# v1_bluetooth-20x20.net
KiCad netlist of a schematic drawn in EAGLE
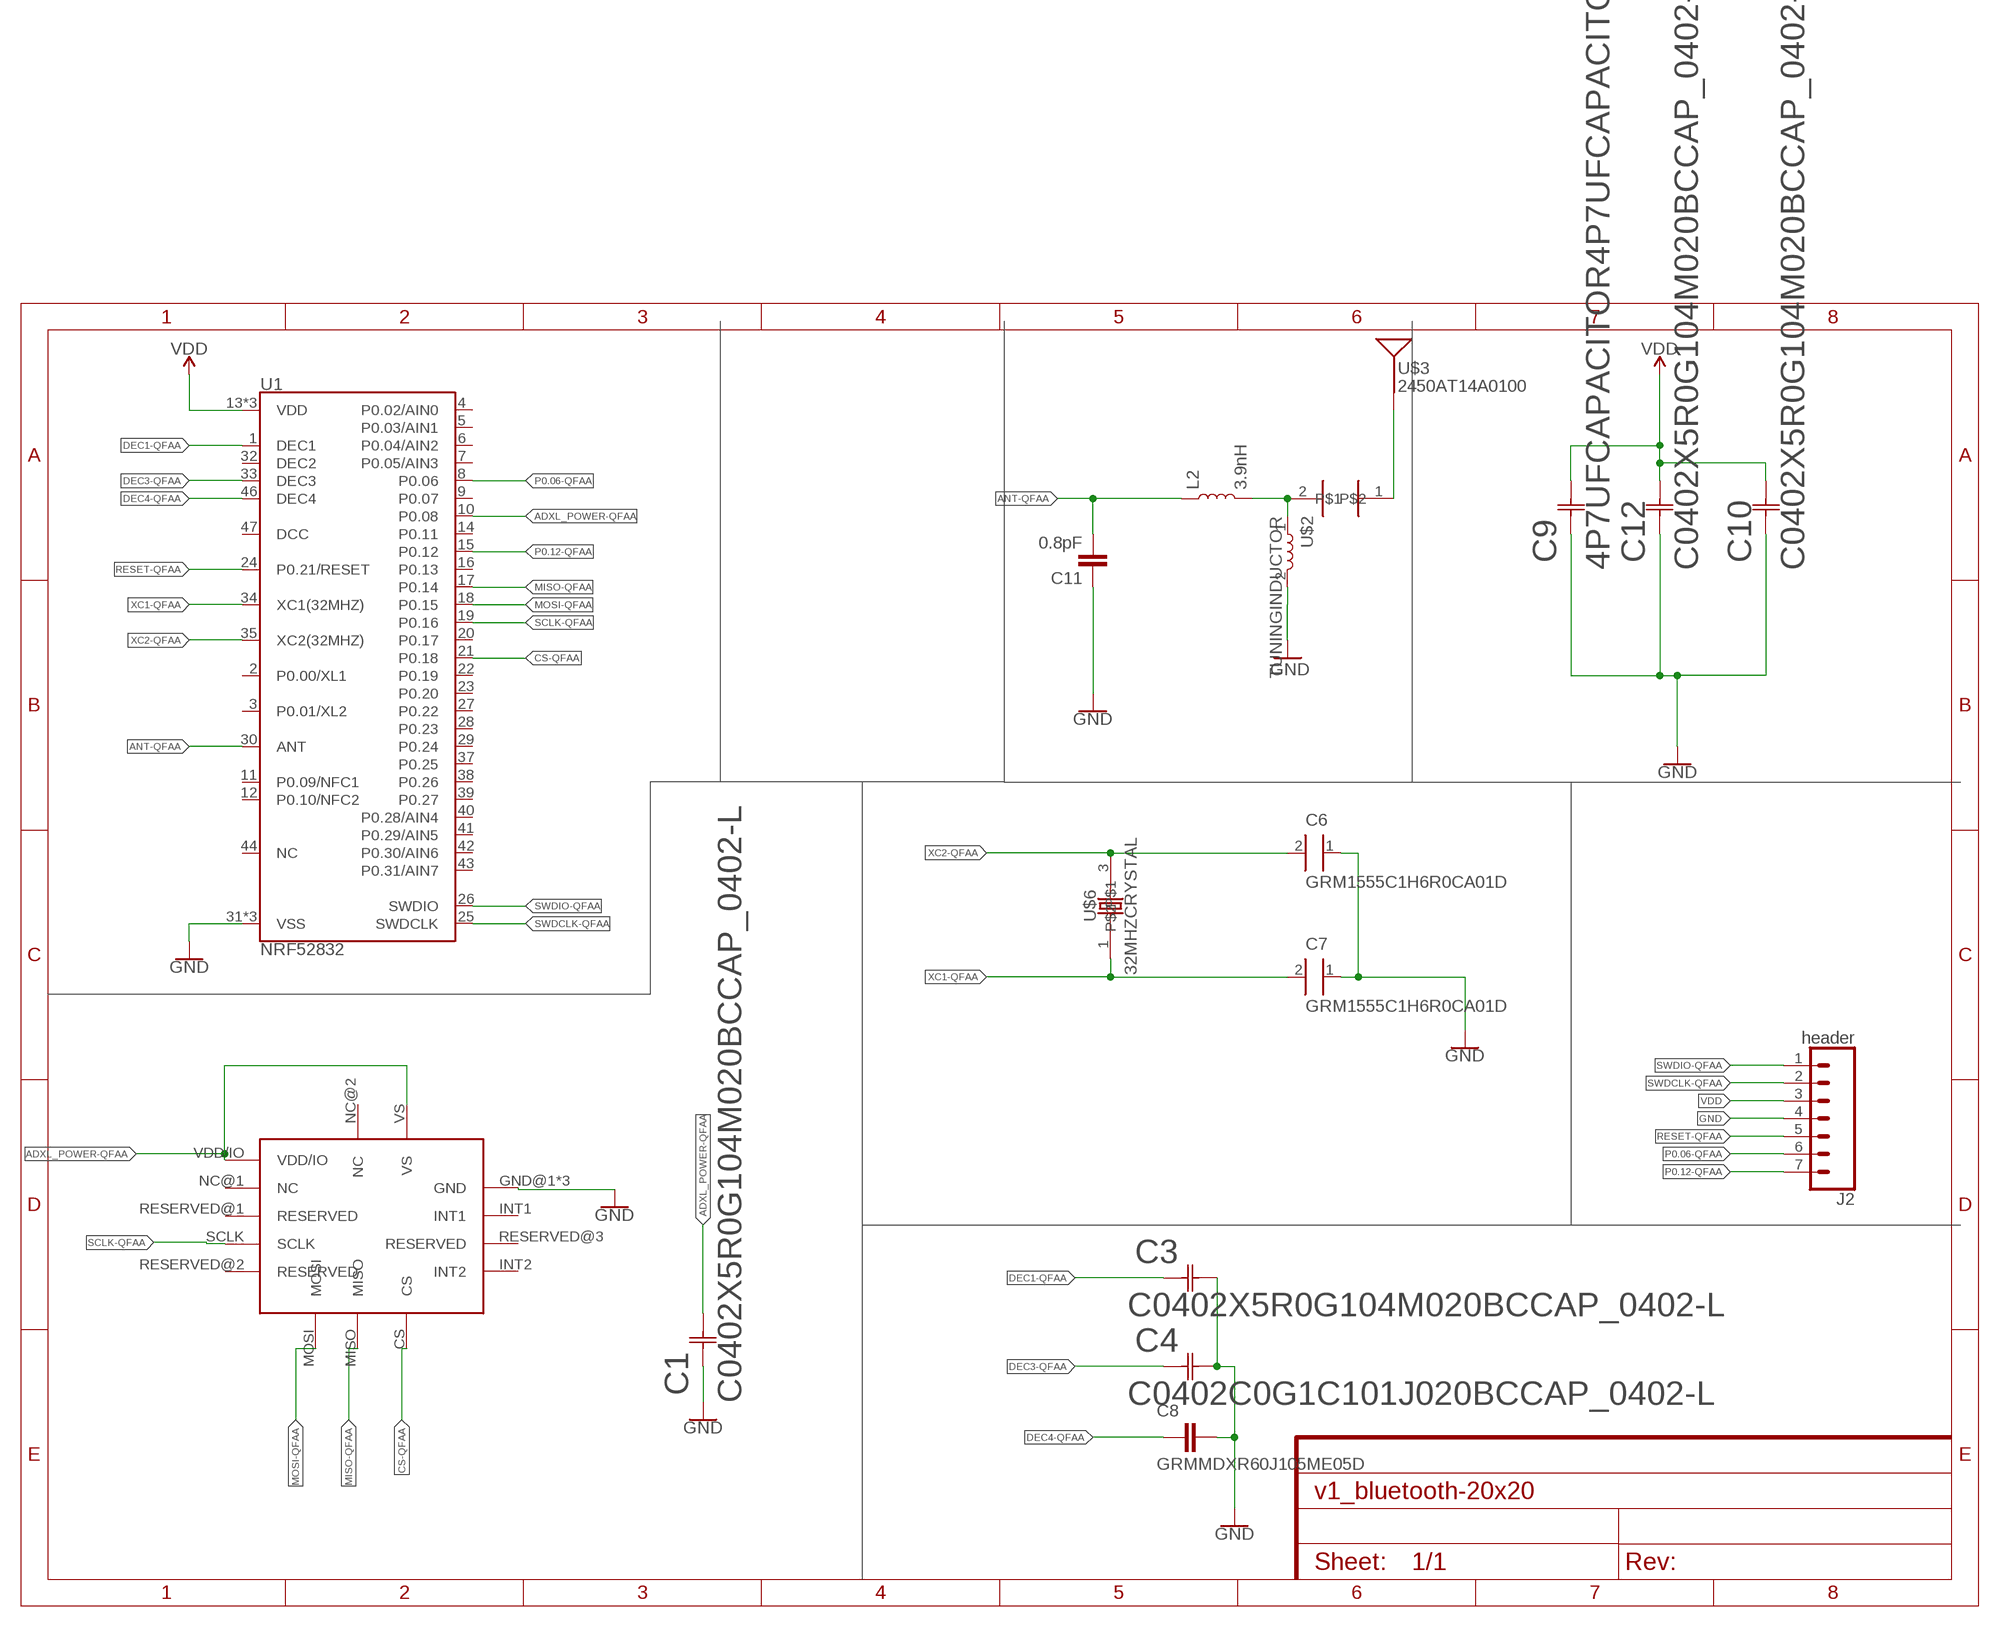
[diagram p0: schematic, sheet 1]

(export (version "E")
  (design (tool "Eeschema 10.0.6"))
  (components
    (comp (ref "C1")
      (value "C0402X5R0G104M020BCCAP_0402-L")
      (footprint "eagle-import:CAP_0402-L")
      (fields (field (name "MANUFACTURER_PART_NUMBER") "C0402C0G1C101J020BC"))
      (libsource (lib "eagle-import") (part "C0402X5R0G104M020BCCAP_0402-L"))
    )
    (comp (ref "C3")
      (value "C0402X5R0G104M020BCCAP_0402-L")
      (footprint "eagle-import:CAP_0402-L")
      (fields (field (name "MANUFACTURER_PART_NUMBER") "C0402C0G1C101J020BC"))
      (libsource (lib "eagle-import") (part "C0402X5R0G104M020BCCAP_0402-L"))
    )
    (comp (ref "C4")
      (value "C0402C0G1C101J020BCCAP_0402-L")
      (footprint "eagle-import:CAP_0402-L")
      (fields (field (name "MANUFACTURER_PART_NUMBER") "C0402C0G1C101J020BC"))
      (libsource (lib "eagle-import") (part "C0402C0G1C101J020BCCAP_0402-L"))
    )
    (comp (ref "C6")
      (value "GRM1555C1H6R0CA01D")
      (footprint "eagle-import:CAPC1005X55N")
      (fields (field (name "DIGI-KEY_PART_NUMBER") "490-8222-1-ND") (field (name "MF") "Murata"))
      (libsource (lib "eagle-import") (part "GRM1555C1H6R0CA01D"))
    )
    (comp (ref "C7")
      (value "GRM1555C1H6R0CA01D")
      (footprint "eagle-import:CAPC1005X55N")
      (fields (field (name "DIGI-KEY_PART_NUMBER") "490-8222-1-ND") (field (name "MF") "Murata"))
      (libsource (lib "eagle-import") (part "GRM1555C1H6R0CA01D"))
    )
    (comp (ref "C8")
      (value "GRMMDXR60J105ME05D")
      (footprint "eagle-import:CAPC0502X28N")
      (fields (field (name "DIGI-KEY_PART_NUMBER") "490-13424-1-ND") (field (name "MF") "Murata"))
      (libsource (lib "eagle-import") (part "GRMMDXR60J105ME05D"))
    )
    (comp (ref "C9")
      (value "4P7UFCAPACITOR4P7UFCAPACITOR")
      (footprint "eagle-import:4P7UFCAPACITOR")
      (fields (field (name "MANUFACTURER_PART_NUMBER") "C0816X5R0J475M050AC"))
      (libsource (lib "eagle-import") (part "4P7UFCAPACITOR4P7UFCAPACITOR"))
    )
    (comp (ref "C10")
      (value "C0402X5R0G104M020BCCAP_0402-L")
      (footprint "eagle-import:CAP_0402-L")
      (fields (field (name "MANUFACTURER_PART_NUMBER") "C0402C0G1C101J020BC"))
      (libsource (lib "eagle-import") (part "C0402X5R0G104M020BCCAP_0402-L"))
    )
    (comp (ref "C11")
      (value "0.8pF")
      (footprint "eagle-import:0402")
      (libsource (lib "eagle-import") (part "0.8PF-0402-50V-0.1PF"))
    )
    (comp (ref "C12")
      (value "C0402X5R0G104M020BCCAP_0402-L")
      (footprint "eagle-import:CAP_0402-L")
      (fields (field (name "MANUFACTURER_PART_NUMBER") "C0402C0G1C101J020BC"))
      (libsource (lib "eagle-import") (part "C0402X5R0G104M020BCCAP_0402-L"))
    )
    (comp (ref "J2")
      (value "header")
      (footprint "eagle-import:1X07")
      (libsource (lib "eagle-import") (part "CONN_07"))
    )
    (comp (ref "L2")
      (value "3.9nH")
      (footprint "eagle-import:0402")
      (libsource (lib "eagle-import") (part "INDUCTOR-0402-3.9NH"))
    )
    (comp (ref "U$1")
      (value "ADXL362")
      (footprint "eagle-import:TFLGA-16_3.3MMX3.1MM")
      (libsource (lib "eagle-import") (part "ADXL362"))
    )
    (comp (ref "U$2")
      (value "TUNINGINDUCTOR")
      (footprint "eagle-import:0402")
      (libsource (lib "eagle-import") (part "TUNINGINDUCTOR"))
    )
    (comp (ref "U$3")
      (value "2450AT14A0100")
      (footprint "eagle-import:2450AT14A0100")
      (libsource (lib "eagle-import") (part "2450AT14A0100"))
    )
    (comp (ref "U$5")
      (value "0402-1005")
      (footprint "eagle-import:0402-1005")
      (libsource (lib "eagle-import") (part "0402-1005"))
    )
    (comp (ref "U$6")
      (value "32MHZCRYSTAL")
      (footprint "eagle-import:32MHZCRYSTAL")
      (libsource (lib "eagle-import") (part "32MHZCRYSTAL"))
    )
    (comp (ref "U1")
      (value "NRF52832")
      (footprint "eagle-import:QFN48-6X6MM")
      (libsource (lib "eagle-import") (part "NRF52832"))
    )
  )
  (nets
    (net (code "1") (name "ADXL_POWER-QFAA") (class "Default")
      (node (ref "C1") (pin "2") (pinfunction "22_2") (pintype "passive"))
      (node (ref "U$1") (pin "VDD/IO") (pinfunction "VDD/IO_VDD/IO") (pintype "bidirectional"))
      (node (ref "U$1") (pin "VS") (pinfunction "VS_VS") (pintype "bidirectional"))
      (node (ref "U1") (pin "10") (pinfunction "P0.08_10") (pintype "bidirectional"))
    )
    (net (code "2") (name "ANT-QFAA") (class "Default")
      (node (ref "C11") (pin "2") (pinfunction "2_2") (pintype "passive"))
      (node (ref "L2") (pin "1") (pinfunction "1_1") (pintype "passive"))
      (node (ref "U1") (pin "30") (pinfunction "ANT_30") (pintype "bidirectional"))
    )
    (net (code "3") (name "CS-QFAA") (class "Default")
      (node (ref "U$1") (pin "CS") (pinfunction "CS_CS") (pintype "bidirectional"))
      (node (ref "U1") (pin "21") (pinfunction "P0.18_21") (pintype "bidirectional"))
    )
    (net (code "4") (name "DEC1-QFAA") (class "Default")
      (node (ref "C3") (pin "1") (pinfunction "11_1") (pintype "passive"))
      (node (ref "U1") (pin "1") (pinfunction "DEC1_1") (pintype "bidirectional"))
    )
    (net (code "5") (name "DEC3-QFAA") (class "Default")
      (node (ref "C4") (pin "1") (pinfunction "11_1") (pintype "passive"))
      (node (ref "U1") (pin "33") (pinfunction "DEC3_33") (pintype "bidirectional"))
    )
    (net (code "6") (name "DEC4-QFAA") (class "Default")
      (node (ref "C8") (pin "1") (pinfunction "1_1") (pintype "passive"))
      (node (ref "U1") (pin "46") (pinfunction "DEC4_46") (pintype "bidirectional"))
    )
    (net (code "7") (name "GND") (class "Default")
      (node (ref "C1") (pin "1") (pinfunction "11_1") (pintype "passive"))
      (node (ref "C10") (pin "1") (pinfunction "11_1") (pintype "passive"))
      (node (ref "C11") (pin "1") (pinfunction "1_1") (pintype "passive"))
      (node (ref "C12") (pin "1") (pinfunction "11_1") (pintype "passive"))
      (node (ref "C3") (pin "2") (pinfunction "22_2") (pintype "passive"))
      (node (ref "C4") (pin "2") (pinfunction "22_2") (pintype "passive"))
      (node (ref "C6") (pin "1") (pinfunction "1_1") (pintype "passive"))
      (node (ref "C7") (pin "1") (pinfunction "1_1") (pintype "passive"))
      (node (ref "C8") (pin "2") (pinfunction "2_2") (pintype "passive"))
      (node (ref "C9") (pin "1") (pinfunction "11_1") (pintype "passive"))
      (node (ref "J2") (pin "4") (pinfunction "4_4") (pintype "passive"))
      (node (ref "U$1") (pin "GND@1") (pinfunction "GND_GND@1") (pintype "bidirectional"))
      (node (ref "U$1") (pin "GND@2") (pinfunction "GND_GND@2") (pintype "bidirectional"))
      (node (ref "U$1") (pin "GND@3") (pinfunction "GND_GND@3") (pintype "bidirectional"))
      (node (ref "U$2") (pin "2") (pinfunction "2_2") (pintype "passive"))
      (node (ref "U1") (pin "31") (pinfunction "VSS_31") (pintype "bidirectional"))
      (node (ref "U1") (pin "45") (pinfunction "VSS_45") (pintype "bidirectional"))
      (node (ref "U1") (pin "EP") (pinfunction "VSS_EP") (pintype "bidirectional"))
    )
    (net (code "8") (name "MISO-QFAA") (class "Default")
      (node (ref "U$1") (pin "MISO") (pinfunction "MISO_MISO") (pintype "bidirectional"))
      (node (ref "U1") (pin "17") (pinfunction "P0.14_17") (pintype "bidirectional"))
    )
    (net (code "9") (name "MOSI-QFAA") (class "Default")
      (node (ref "U$1") (pin "MOSI") (pinfunction "MOSI_MOSI") (pintype "bidirectional"))
      (node (ref "U1") (pin "18") (pinfunction "P0.15_18") (pintype "bidirectional"))
    )
    (net (code "10") (name "Net-(U$3-SIGNAL)") (class "Default")
      (node (ref "U$3") (pin "FEED") (pinfunction "SIGNAL_FEED") (pintype "bidirectional"))
      (node (ref "U$5") (pin "1") (pinfunction "P$1_1") (pintype "bidirectional"))
    )
    (net (code "11") (name "Net-(U$5-P$2)") (class "Default")
      (node (ref "L2") (pin "2") (pinfunction "2_2") (pintype "passive"))
      (node (ref "U$2") (pin "1") (pinfunction "1_1") (pintype "passive"))
      (node (ref "U$5") (pin "2") (pinfunction "P$2_2") (pintype "bidirectional"))
    )
    (net (code "12") (name "P0.06-QFAA") (class "Default")
      (node (ref "J2") (pin "6") (pinfunction "6_6") (pintype "passive"))
      (node (ref "U1") (pin "8") (pinfunction "P0.06_8") (pintype "bidirectional"))
    )
    (net (code "13") (name "P0.12-QFAA") (class "Default")
      (node (ref "J2") (pin "7") (pinfunction "7_7") (pintype "passive"))
      (node (ref "U1") (pin "15") (pinfunction "P0.12_15") (pintype "bidirectional"))
    )
    (net (code "14") (name "RESET-QFAA") (class "Default")
      (node (ref "J2") (pin "5") (pinfunction "5_5") (pintype "passive"))
      (node (ref "U1") (pin "24") (pinfunction "P0.21/RESET_24") (pintype "bidirectional"))
    )
    (net (code "15") (name "SCLK-QFAA") (class "Default")
      (node (ref "U$1") (pin "SCLK") (pinfunction "SCLK_SCLK") (pintype "bidirectional"))
      (node (ref "U1") (pin "19") (pinfunction "P0.16_19") (pintype "bidirectional"))
    )
    (net (code "16") (name "SWDCLK-QFAA") (class "Default")
      (node (ref "J2") (pin "2") (pinfunction "2_2") (pintype "passive"))
      (node (ref "U1") (pin "25") (pinfunction "SWDCLK_25") (pintype "bidirectional"))
    )
    (net (code "17") (name "SWDIO-QFAA") (class "Default")
      (node (ref "J2") (pin "1") (pinfunction "1_1") (pintype "passive"))
      (node (ref "U1") (pin "26") (pinfunction "SWDIO_26") (pintype "bidirectional"))
    )
    (net (code "18") (name "VDD") (class "Default")
      (node (ref "C10") (pin "2") (pinfunction "22_2") (pintype "passive"))
      (node (ref "C12") (pin "2") (pinfunction "22_2") (pintype "passive"))
      (node (ref "C9") (pin "2") (pinfunction "22_2") (pintype "passive"))
      (node (ref "J2") (pin "3") (pinfunction "3_3") (pintype "passive"))
      (node (ref "U1") (pin "13") (pinfunction "VDD_13") (pintype "bidirectional"))
      (node (ref "U1") (pin "36") (pinfunction "VDD_36") (pintype "bidirectional"))
      (node (ref "U1") (pin "48") (pinfunction "VDD_48") (pintype "bidirectional"))
    )
    (net (code "19") (name "XC1-QFAA") (class "Default")
      (node (ref "C7") (pin "2") (pinfunction "2_2") (pintype "passive"))
      (node (ref "U$6") (pin "1") (pinfunction "P$1_1") (pintype "bidirectional"))
      (node (ref "U1") (pin "34") (pinfunction "XC1(32MHZ)_34") (pintype "bidirectional"))
    )
    (net (code "20") (name "XC2-QFAA") (class "Default")
      (node (ref "C6") (pin "2") (pinfunction "2_2") (pintype "passive"))
      (node (ref "U$6") (pin "3") (pinfunction "P$2_3") (pintype "bidirectional"))
      (node (ref "U1") (pin "35") (pinfunction "XC2(32MHZ)_35") (pintype "bidirectional"))
    )
    (net (code "21") (name "unconnected-(U$1-NC-PadNC@1)") (class "Default")
      (node (ref "U$1") (pin "NC@1") (pinfunction "NC_NC@1") (pintype "bidirectional"))
    )
    (net (code "22") (name "unconnected-(U$1-NC-PadNC@2)") (class "Default")
      (node (ref "U$1") (pin "NC@2") (pinfunction "NC_NC@2") (pintype "bidirectional"))
    )
    (net (code "23") (name "unconnected-(U$1-PadINT1)") (class "Default")
      (node (ref "U$1") (pin "INT1") (pinfunction "INT1_INT1") (pintype "bidirectional"))
    )
    (net (code "24") (name "unconnected-(U$1-PadINT2)") (class "Default")
      (node (ref "U$1") (pin "INT2") (pinfunction "INT2_INT2") (pintype "bidirectional"))
    )
    (net (code "25") (name "unconnected-(U$1-RESERVED-PadRESERVED@1)") (class "Default")
      (node (ref "U$1") (pin "RESERVED@1") (pinfunction "RESERVED_RESERVED@1") (pintype "bidirectional"))
    )
    (net (code "26") (name "unconnected-(U$1-RESERVED-PadRESERVED@2)") (class "Default")
      (node (ref "U$1") (pin "RESERVED@2") (pinfunction "RESERVED_RESERVED@2") (pintype "bidirectional"))
    )
    (net (code "27") (name "unconnected-(U$1-RESERVED-PadRESERVED@3)") (class "Default")
      (node (ref "U$1") (pin "RESERVED@3") (pinfunction "RESERVED_RESERVED@3") (pintype "bidirectional"))
    )
    (net (code "28") (name "unconnected-(U1-DCC-Pad47)") (class "Default")
      (node (ref "U1") (pin "47") (pinfunction "DCC_47") (pintype "bidirectional"))
    )
    (net (code "29") (name "unconnected-(U1-DEC2-Pad32)") (class "Default")
      (node (ref "U1") (pin "32") (pinfunction "DEC2_32") (pintype "bidirectional"))
    )
    (net (code "30") (name "unconnected-(U1-NC-Pad44)") (class "Default")
      (node (ref "U1") (pin "44") (pinfunction "NC_44") (pintype "bidirectional"))
    )
    (net (code "31") (name "unconnected-(U1-P0.00{slash}XL1-Pad2)") (class "Default")
      (node (ref "U1") (pin "2") (pinfunction "P0.00/XL1_2") (pintype "bidirectional"))
    )
    (net (code "32") (name "unconnected-(U1-P0.01{slash}XL2-Pad3)") (class "Default")
      (node (ref "U1") (pin "3") (pinfunction "P0.01/XL2_3") (pintype "bidirectional"))
    )
    (net (code "33") (name "unconnected-(U1-P0.02{slash}AIN0-Pad4)") (class "Default")
      (node (ref "U1") (pin "4") (pinfunction "P0.02/AIN0_4") (pintype "bidirectional"))
    )
    (net (code "34") (name "unconnected-(U1-P0.03{slash}AIN1-Pad5)") (class "Default")
      (node (ref "U1") (pin "5") (pinfunction "P0.03/AIN1_5") (pintype "bidirectional"))
    )
    (net (code "35") (name "unconnected-(U1-P0.04{slash}AIN2-Pad6)") (class "Default")
      (node (ref "U1") (pin "6") (pinfunction "P0.04/AIN2_6") (pintype "bidirectional"))
    )
    (net (code "36") (name "unconnected-(U1-P0.05{slash}AIN3-Pad7)") (class "Default")
      (node (ref "U1") (pin "7") (pinfunction "P0.05/AIN3_7") (pintype "bidirectional"))
    )
    (net (code "37") (name "unconnected-(U1-P0.07-Pad9)") (class "Default")
      (node (ref "U1") (pin "9") (pinfunction "P0.07_9") (pintype "bidirectional"))
    )
    (net (code "38") (name "unconnected-(U1-P0.09{slash}NFC1-Pad11)") (class "Default")
      (node (ref "U1") (pin "11") (pinfunction "P0.09/NFC1_11") (pintype "bidirectional"))
    )
    (net (code "39") (name "unconnected-(U1-P0.10{slash}NFC2-Pad12)") (class "Default")
      (node (ref "U1") (pin "12") (pinfunction "P0.10/NFC2_12") (pintype "bidirectional"))
    )
    (net (code "40") (name "unconnected-(U1-P0.11-Pad14)") (class "Default")
      (node (ref "U1") (pin "14") (pinfunction "P0.11_14") (pintype "bidirectional"))
    )
    (net (code "41") (name "unconnected-(U1-P0.13-Pad16)") (class "Default")
      (node (ref "U1") (pin "16") (pinfunction "P0.13_16") (pintype "bidirectional"))
    )
    (net (code "42") (name "unconnected-(U1-P0.17-Pad20)") (class "Default")
      (node (ref "U1") (pin "20") (pinfunction "P0.17_20") (pintype "bidirectional"))
    )
    (net (code "43") (name "unconnected-(U1-P0.19-Pad22)") (class "Default")
      (node (ref "U1") (pin "22") (pinfunction "P0.19_22") (pintype "bidirectional"))
    )
    (net (code "44") (name "unconnected-(U1-P0.20-Pad23)") (class "Default")
      (node (ref "U1") (pin "23") (pinfunction "P0.20_23") (pintype "bidirectional"))
    )
    (net (code "45") (name "unconnected-(U1-P0.22-Pad27)") (class "Default")
      (node (ref "U1") (pin "27") (pinfunction "P0.22_27") (pintype "bidirectional"))
    )
    (net (code "46") (name "unconnected-(U1-P0.23-Pad28)") (class "Default")
      (node (ref "U1") (pin "28") (pinfunction "P0.23_28") (pintype "bidirectional"))
    )
    (net (code "47") (name "unconnected-(U1-P0.24-Pad29)") (class "Default")
      (node (ref "U1") (pin "29") (pinfunction "P0.24_29") (pintype "bidirectional"))
    )
    (net (code "48") (name "unconnected-(U1-P0.25-Pad37)") (class "Default")
      (node (ref "U1") (pin "37") (pinfunction "P0.25_37") (pintype "bidirectional"))
    )
    (net (code "49") (name "unconnected-(U1-P0.26-Pad38)") (class "Default")
      (node (ref "U1") (pin "38") (pinfunction "P0.26_38") (pintype "bidirectional"))
    )
    (net (code "50") (name "unconnected-(U1-P0.27-Pad39)") (class "Default")
      (node (ref "U1") (pin "39") (pinfunction "P0.27_39") (pintype "bidirectional"))
    )
    (net (code "51") (name "unconnected-(U1-P0.28{slash}AIN4-Pad40)") (class "Default")
      (node (ref "U1") (pin "40") (pinfunction "P0.28/AIN4_40") (pintype "bidirectional"))
    )
    (net (code "52") (name "unconnected-(U1-P0.29{slash}AIN5-Pad41)") (class "Default")
      (node (ref "U1") (pin "41") (pinfunction "P0.29/AIN5_41") (pintype "bidirectional"))
    )
    (net (code "53") (name "unconnected-(U1-P0.30{slash}AIN6-Pad42)") (class "Default")
      (node (ref "U1") (pin "42") (pinfunction "P0.30/AIN6_42") (pintype "bidirectional"))
    )
    (net (code "54") (name "unconnected-(U1-P0.31{slash}AIN7-Pad43)") (class "Default")
      (node (ref "U1") (pin "43") (pinfunction "P0.31/AIN7_43") (pintype "bidirectional"))
    )
  )
)
